# 02_Power.net
KiCad netlist of a schematic drawn in Altium Designer
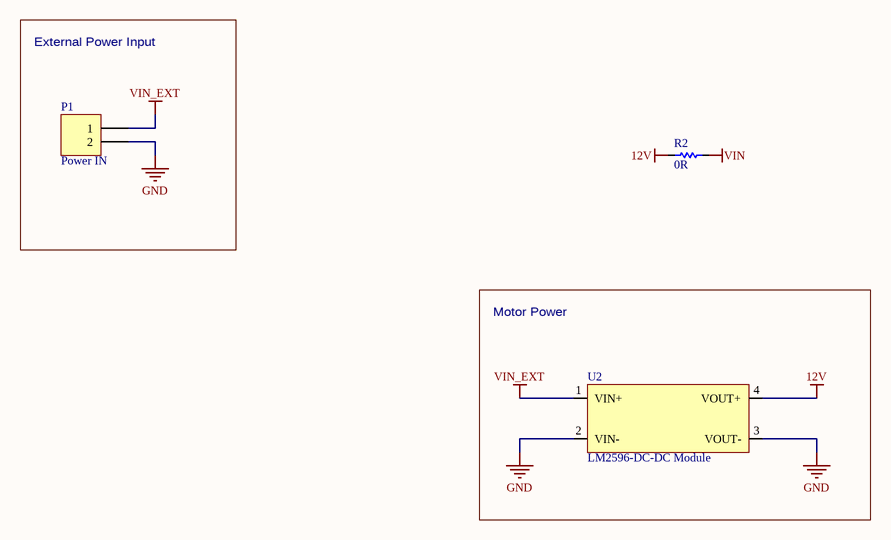
[diagram p0: 02_Power.SchDoc]

(export (version "E")
  (design (tool "Eeschema 10.0.6"))
  (components
    (comp (ref "P1")
      (value "Power IN")
      (footprint "Footprint_Misc:TERMINAL_2POS_90DEG_2PART")
      (fields
        (field (name "MANUFACTURER") "Würth Elektronik")
        (field (name "MANUFACTURER PART NUMBER") "691322110002")
        (field (name "DISTRIBUTOR PART NUMBER") "732-2769-ND")
      )
      (libsource (lib "Schematic_Misc") (part "Terminal 2_691322110002"))
    )
    (comp (ref "R2")
      (value "0R")
      (footprint "Moji Footprintovi:0603")
      (description "Resistor")
      (fields
        (field (name "DISTRIBUTOR PART NUMBER") "13-RC0603FR-130RLCT-ND")
        (field (name "MANUFACTURER") "YAGEO")
      )
      (libsource (lib "Schematic_Misc") (part "Res"))
    )
    (comp (ref "U2")
      (value "LM2596-DC-DC Module")
      (footprint "Moji Footprintovi:LM2596-DC-DC Module")
      (description "LM2596-DC-DC Module HW-411")
      (fields
        (field (name "DISTRIBUTOR PART NUMBER") "https://www.aliexpress.com/item/33004374185.html")
        (field (name "MANUFACTURER PART NUMBER") "LM2596-DC-DC")
      )
      (libsource (lib "Moji Schematici") (part "LM2596-DC-DC Module"))
    )
  )
  (nets
    (net (code "1") (name "12V") (class "Default")
      (node (ref "R2") (pin "2") (pinfunction "2_2") (pintype "passive"))
      (node (ref "U2") (pin "4") (pinfunction "VOUT+_4") (pintype "passive"))
    )
    (net (code "2") (name "GND") (class "Default")
      (node (ref "P1") (pin "2") (pinfunction "2_2") (pintype "passive"))
      (node (ref "U2") (pin "2") (pinfunction "VIN-_2") (pintype "passive"))
      (node (ref "U2") (pin "3") (pinfunction "VOUT-_3") (pintype "passive"))
    )
    (net (code "3") (name "VIN") (class "Default")
      (node (ref "R2") (pin "1") (pinfunction "1_1") (pintype "passive"))
    )
    (net (code "4") (name "VIN_EXT") (class "Default")
      (node (ref "P1") (pin "1") (pinfunction "1_1") (pintype "passive"))
      (node (ref "U2") (pin "1") (pinfunction "VIN+_1") (pintype "passive"))
    )
  )
)
